# UI.net
KiCad netlist of a schematic drawn in Altium Designer
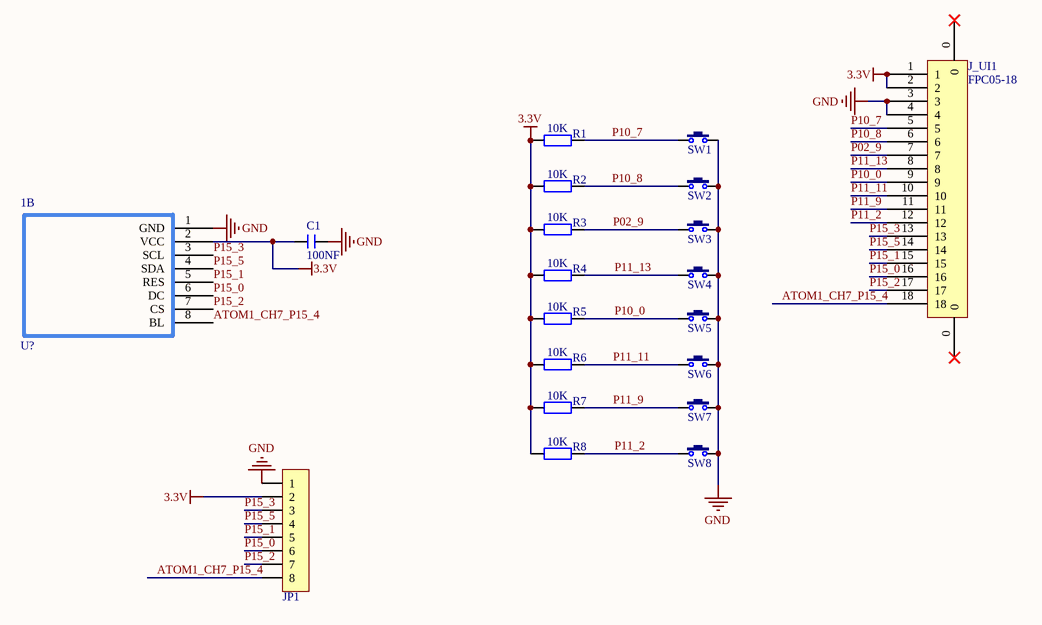
[diagram p0: UI.SchDoc]

(export (version "E")
  (design (tool "Eeschema 10.0.6"))
  (components
    (comp (ref "1") (value "U?") (footprint "1.8'TFT") (libsource (lib "1.8'TFT") (part "1.8'TFT")))
    (comp (ref "C1")
      (value "100NF")
      (footprint "C 0805_L")
      (description "无极性贴片电容")
      (fields (field (name "版权归属") "源创客"))
      (libsource (lib "3.1   - 电阻-电容-电感") (part "C"))
    )
    (comp (ref "JP1")
      (value "HDR-1X8")
      (footprint "HDR2.54-LI-8P")
      (description "8P接插件")
      (fields (field (name "版权归属") "源创客"))
      (libsource (lib "4.6   - 接插件-脚距2.54") (part "Header 8"))
    )
    (comp (ref "J_UI1")
      (value "FPC05-18")
      (footprint "FPC-05mm-18")
      (libsource (lib "FPC18") (part "FPC05-18"))
    )
    (comp (ref "R1")
      (value "10K")
      (footprint "R 0805_L")
      (description "贴片电阻")
      (fields (field (name "版权归属") "源创客"))
      (libsource (lib "3.1   - 电阻-电容-电感") (part "R"))
    )
    (comp (ref "R2")
      (value "10K")
      (footprint "R 0805_L")
      (description "贴片电阻")
      (fields (field (name "版权归属") "源创客"))
      (libsource (lib "3.1   - 电阻-电容-电感") (part "R"))
    )
    (comp (ref "R3")
      (value "10K")
      (footprint "R 0805_L")
      (description "贴片电阻")
      (fields (field (name "版权归属") "源创客"))
      (libsource (lib "3.1   - 电阻-电容-电感") (part "R"))
    )
    (comp (ref "R4")
      (value "10K")
      (footprint "R 0805_L")
      (description "贴片电阻")
      (fields (field (name "版权归属") "源创客"))
      (libsource (lib "3.1   - 电阻-电容-电感") (part "R"))
    )
    (comp (ref "R5")
      (value "10K")
      (footprint "R 0805_L")
      (description "贴片电阻")
      (fields (field (name "版权归属") "源创客"))
      (libsource (lib "3.1   - 电阻-电容-电感") (part "R"))
    )
    (comp (ref "R6")
      (value "10K")
      (footprint "R 0805_L")
      (description "贴片电阻")
      (fields (field (name "版权归属") "源创客"))
      (libsource (lib "3.1   - 电阻-电容-电感") (part "R"))
    )
    (comp (ref "R7")
      (value "10K")
      (footprint "R 0805_L")
      (description "贴片电阻")
      (fields (field (name "版权归属") "源创客"))
      (libsource (lib "3.1   - 电阻-电容-电感") (part "R"))
    )
    (comp (ref "R8")
      (value "10K")
      (footprint "R 0805_L")
      (description "贴片电阻")
      (fields (field (name "版权归属") "源创客"))
      (libsource (lib "3.1   - 电阻-电容-电感") (part "R"))
    )
    (comp (ref "SW1")
      (value "3x6x5")
      (footprint "TSW SMD-3*6*2.5")
      (description "3x6轻触开关")
      (fields (field (name "版权归属") "源创客"))
      (libsource (lib "5.1   - 按键-开关") (part "TSW 3x6"))
    )
    (comp (ref "SW2")
      (value "3x6x5")
      (footprint "TSW SMD-3*6*2.5")
      (description "3x6轻触开关")
      (fields (field (name "版权归属") "源创客"))
      (libsource (lib "5.1   - 按键-开关") (part "TSW 3x6"))
    )
    (comp (ref "SW3")
      (value "3x6x5")
      (footprint "TSW SMD-3*6*2.5")
      (description "3x6轻触开关")
      (fields (field (name "版权归属") "源创客"))
      (libsource (lib "5.1   - 按键-开关") (part "TSW 3x6"))
    )
    (comp (ref "SW4")
      (value "3x6x5")
      (footprint "TSW SMD-3*6*2.5")
      (description "3x6轻触开关")
      (fields (field (name "版权归属") "源创客"))
      (libsource (lib "5.1   - 按键-开关") (part "TSW 3x6"))
    )
    (comp (ref "SW5")
      (value "3x6x5")
      (footprint "TSW SMD-3*6*2.5")
      (description "3x6轻触开关")
      (fields (field (name "版权归属") "源创客"))
      (libsource (lib "5.1   - 按键-开关") (part "TSW 3x6"))
    )
    (comp (ref "SW6")
      (value "3x6x5")
      (footprint "TSW SMD-3*6*2.5")
      (description "3x6轻触开关")
      (fields (field (name "版权归属") "源创客"))
      (libsource (lib "5.1   - 按键-开关") (part "TSW 3x6"))
    )
    (comp (ref "SW7")
      (value "3x6x5")
      (footprint "TSW SMD-3*6*2.5")
      (description "3x6轻触开关")
      (fields (field (name "版权归属") "源创客"))
      (libsource (lib "5.1   - 按键-开关") (part "TSW 3x6"))
    )
    (comp (ref "SW8")
      (value "3x6x5")
      (footprint "TSW SMD-3*6*2.5")
      (description "3x6轻触开关")
      (fields (field (name "版权归属") "源创客"))
      (libsource (lib "5.1   - 按键-开关") (part "TSW 3x6"))
    )
  )
  (nets
    (net (code "1") (name "/ATOM1_CH7_P15_4") (class "Default")
      (node (ref "1") (pin "8") (pinfunction "BL_8") (pintype "passive"))
      (node (ref "JP1") (pin "8") (pinfunction "8_8") (pintype "passive"))
      (node (ref "J_UI1") (pin "18") (pinfunction "18_18") (pintype "passive"))
    )
    (net (code "2") (name "/P02_9") (class "Default")
      (node (ref "J_UI1") (pin "7") (pinfunction "7_7") (pintype "passive"))
      (node (ref "R3") (pin "2") (pinfunction "2_2") (pintype "passive"))
      (node (ref "SW3") (pin "1") (pinfunction "1_1") (pintype "passive"))
    )
    (net (code "3") (name "/P10_0") (class "Default")
      (node (ref "J_UI1") (pin "9") (pinfunction "9_9") (pintype "passive"))
      (node (ref "R5") (pin "2") (pinfunction "2_2") (pintype "passive"))
      (node (ref "SW5") (pin "1") (pinfunction "1_1") (pintype "passive"))
    )
    (net (code "4") (name "/P10_7") (class "Default")
      (node (ref "J_UI1") (pin "5") (pinfunction "5_5") (pintype "passive"))
      (node (ref "R1") (pin "2") (pinfunction "2_2") (pintype "passive"))
      (node (ref "SW1") (pin "1") (pinfunction "1_1") (pintype "passive"))
    )
    (net (code "5") (name "/P10_8") (class "Default")
      (node (ref "J_UI1") (pin "6") (pinfunction "6_6") (pintype "passive"))
      (node (ref "R2") (pin "2") (pinfunction "2_2") (pintype "passive"))
      (node (ref "SW2") (pin "1") (pinfunction "1_1") (pintype "passive"))
    )
    (net (code "6") (name "/P11_2") (class "Default")
      (node (ref "J_UI1") (pin "12") (pinfunction "12_12") (pintype "passive"))
      (node (ref "R8") (pin "2") (pinfunction "2_2") (pintype "passive"))
      (node (ref "SW8") (pin "1") (pinfunction "1_1") (pintype "passive"))
    )
    (net (code "7") (name "/P11_9") (class "Default")
      (node (ref "J_UI1") (pin "11") (pinfunction "11_11") (pintype "passive"))
      (node (ref "R7") (pin "2") (pinfunction "2_2") (pintype "passive"))
      (node (ref "SW7") (pin "1") (pinfunction "1_1") (pintype "passive"))
    )
    (net (code "8") (name "/P11_11") (class "Default")
      (node (ref "J_UI1") (pin "10") (pinfunction "10_10") (pintype "passive"))
      (node (ref "R6") (pin "2") (pinfunction "2_2") (pintype "passive"))
      (node (ref "SW6") (pin "1") (pinfunction "1_1") (pintype "passive"))
    )
    (net (code "9") (name "/P11_13") (class "Default")
      (node (ref "J_UI1") (pin "8") (pinfunction "8_8") (pintype "passive"))
      (node (ref "R4") (pin "2") (pinfunction "2_2") (pintype "passive"))
      (node (ref "SW4") (pin "1") (pinfunction "1_1") (pintype "passive"))
    )
    (net (code "10") (name "/P15_0") (class "Default")
      (node (ref "1") (pin "6") (pinfunction "DC_6") (pintype "passive"))
      (node (ref "JP1") (pin "6") (pinfunction "6_6") (pintype "passive"))
      (node (ref "J_UI1") (pin "16") (pinfunction "16_16") (pintype "passive"))
    )
    (net (code "11") (name "/P15_1") (class "Default")
      (node (ref "1") (pin "5") (pinfunction "RES_5") (pintype "passive"))
      (node (ref "JP1") (pin "5") (pinfunction "5_5") (pintype "passive"))
      (node (ref "J_UI1") (pin "15") (pinfunction "15_15") (pintype "passive"))
    )
    (net (code "12") (name "/P15_2") (class "Default")
      (node (ref "1") (pin "7") (pinfunction "CS_7") (pintype "passive"))
      (node (ref "JP1") (pin "7") (pinfunction "7_7") (pintype "passive"))
      (node (ref "J_UI1") (pin "17") (pinfunction "17_17") (pintype "passive"))
    )
    (net (code "13") (name "/P15_3") (class "Default")
      (node (ref "1") (pin "3") (pinfunction "SCL_3") (pintype "passive"))
      (node (ref "JP1") (pin "3") (pinfunction "3_3") (pintype "passive"))
      (node (ref "J_UI1") (pin "13") (pinfunction "13_13") (pintype "passive"))
    )
    (net (code "14") (name "/P15_5") (class "Default")
      (node (ref "1") (pin "4") (pinfunction "SDA_4") (pintype "passive"))
      (node (ref "JP1") (pin "4") (pinfunction "4_4") (pintype "passive"))
      (node (ref "J_UI1") (pin "14") (pinfunction "14_14") (pintype "passive"))
    )
    (net (code "15") (name "3.3V") (class "Default")
      (node (ref "1") (pin "2") (pinfunction "VCC_2") (pintype "passive"))
      (node (ref "C1") (pin "2") (pinfunction "2_2") (pintype "passive"))
      (node (ref "JP1") (pin "2") (pinfunction "2_2") (pintype "passive"))
      (node (ref "J_UI1") (pin "1") (pinfunction "1_1") (pintype "passive"))
      (node (ref "J_UI1") (pin "2") (pinfunction "2_2") (pintype "passive"))
      (node (ref "R1") (pin "1") (pinfunction "1_1") (pintype "passive"))
      (node (ref "R2") (pin "1") (pinfunction "1_1") (pintype "passive"))
      (node (ref "R3") (pin "1") (pinfunction "1_1") (pintype "passive"))
      (node (ref "R4") (pin "1") (pinfunction "1_1") (pintype "passive"))
      (node (ref "R5") (pin "1") (pinfunction "1_1") (pintype "passive"))
      (node (ref "R6") (pin "1") (pinfunction "1_1") (pintype "passive"))
      (node (ref "R7") (pin "1") (pinfunction "1_1") (pintype "passive"))
      (node (ref "R8") (pin "1") (pinfunction "1_1") (pintype "passive"))
    )
    (net (code "16") (name "GND") (class "Default")
      (node (ref "1") (pin "1") (pinfunction "GND_1") (pintype "passive"))
      (node (ref "C1") (pin "1") (pinfunction "1_1") (pintype "passive"))
      (node (ref "JP1") (pin "1") (pinfunction "1_1") (pintype "passive"))
      (node (ref "J_UI1") (pin "3") (pinfunction "3_3") (pintype "passive"))
      (node (ref "J_UI1") (pin "4") (pinfunction "4_4") (pintype "passive"))
      (node (ref "SW1") (pin "2") (pinfunction "2_2") (pintype "passive"))
      (node (ref "SW2") (pin "2") (pinfunction "2_2") (pintype "passive"))
      (node (ref "SW3") (pin "2") (pinfunction "2_2") (pintype "passive"))
      (node (ref "SW4") (pin "2") (pinfunction "2_2") (pintype "passive"))
      (node (ref "SW5") (pin "2") (pinfunction "2_2") (pintype "passive"))
      (node (ref "SW6") (pin "2") (pinfunction "2_2") (pintype "passive"))
      (node (ref "SW7") (pin "2") (pinfunction "2_2") (pintype "passive"))
      (node (ref "SW8") (pin "2") (pinfunction "2_2") (pintype "passive"))
    )
    (net (code "17") (name "unconnected-(J_UI1-Pad0)") (class "Default")
      (node (ref "J_UI1") (pin "0") (pinfunction "0_0") (pintype "passive+no_connect"))
    )
    (net (code "18") (name "unconnected-(J_UI1-Pad0)_1") (class "Default")
      (node (ref "J_UI1") (pin "0") (pinfunction "0_0") (pintype "passive+no_connect"))
    )
  )
)
